# SCH_555-Circuit_2025-10-18.net
KiCad netlist of a schematic drawn in EasyEDA
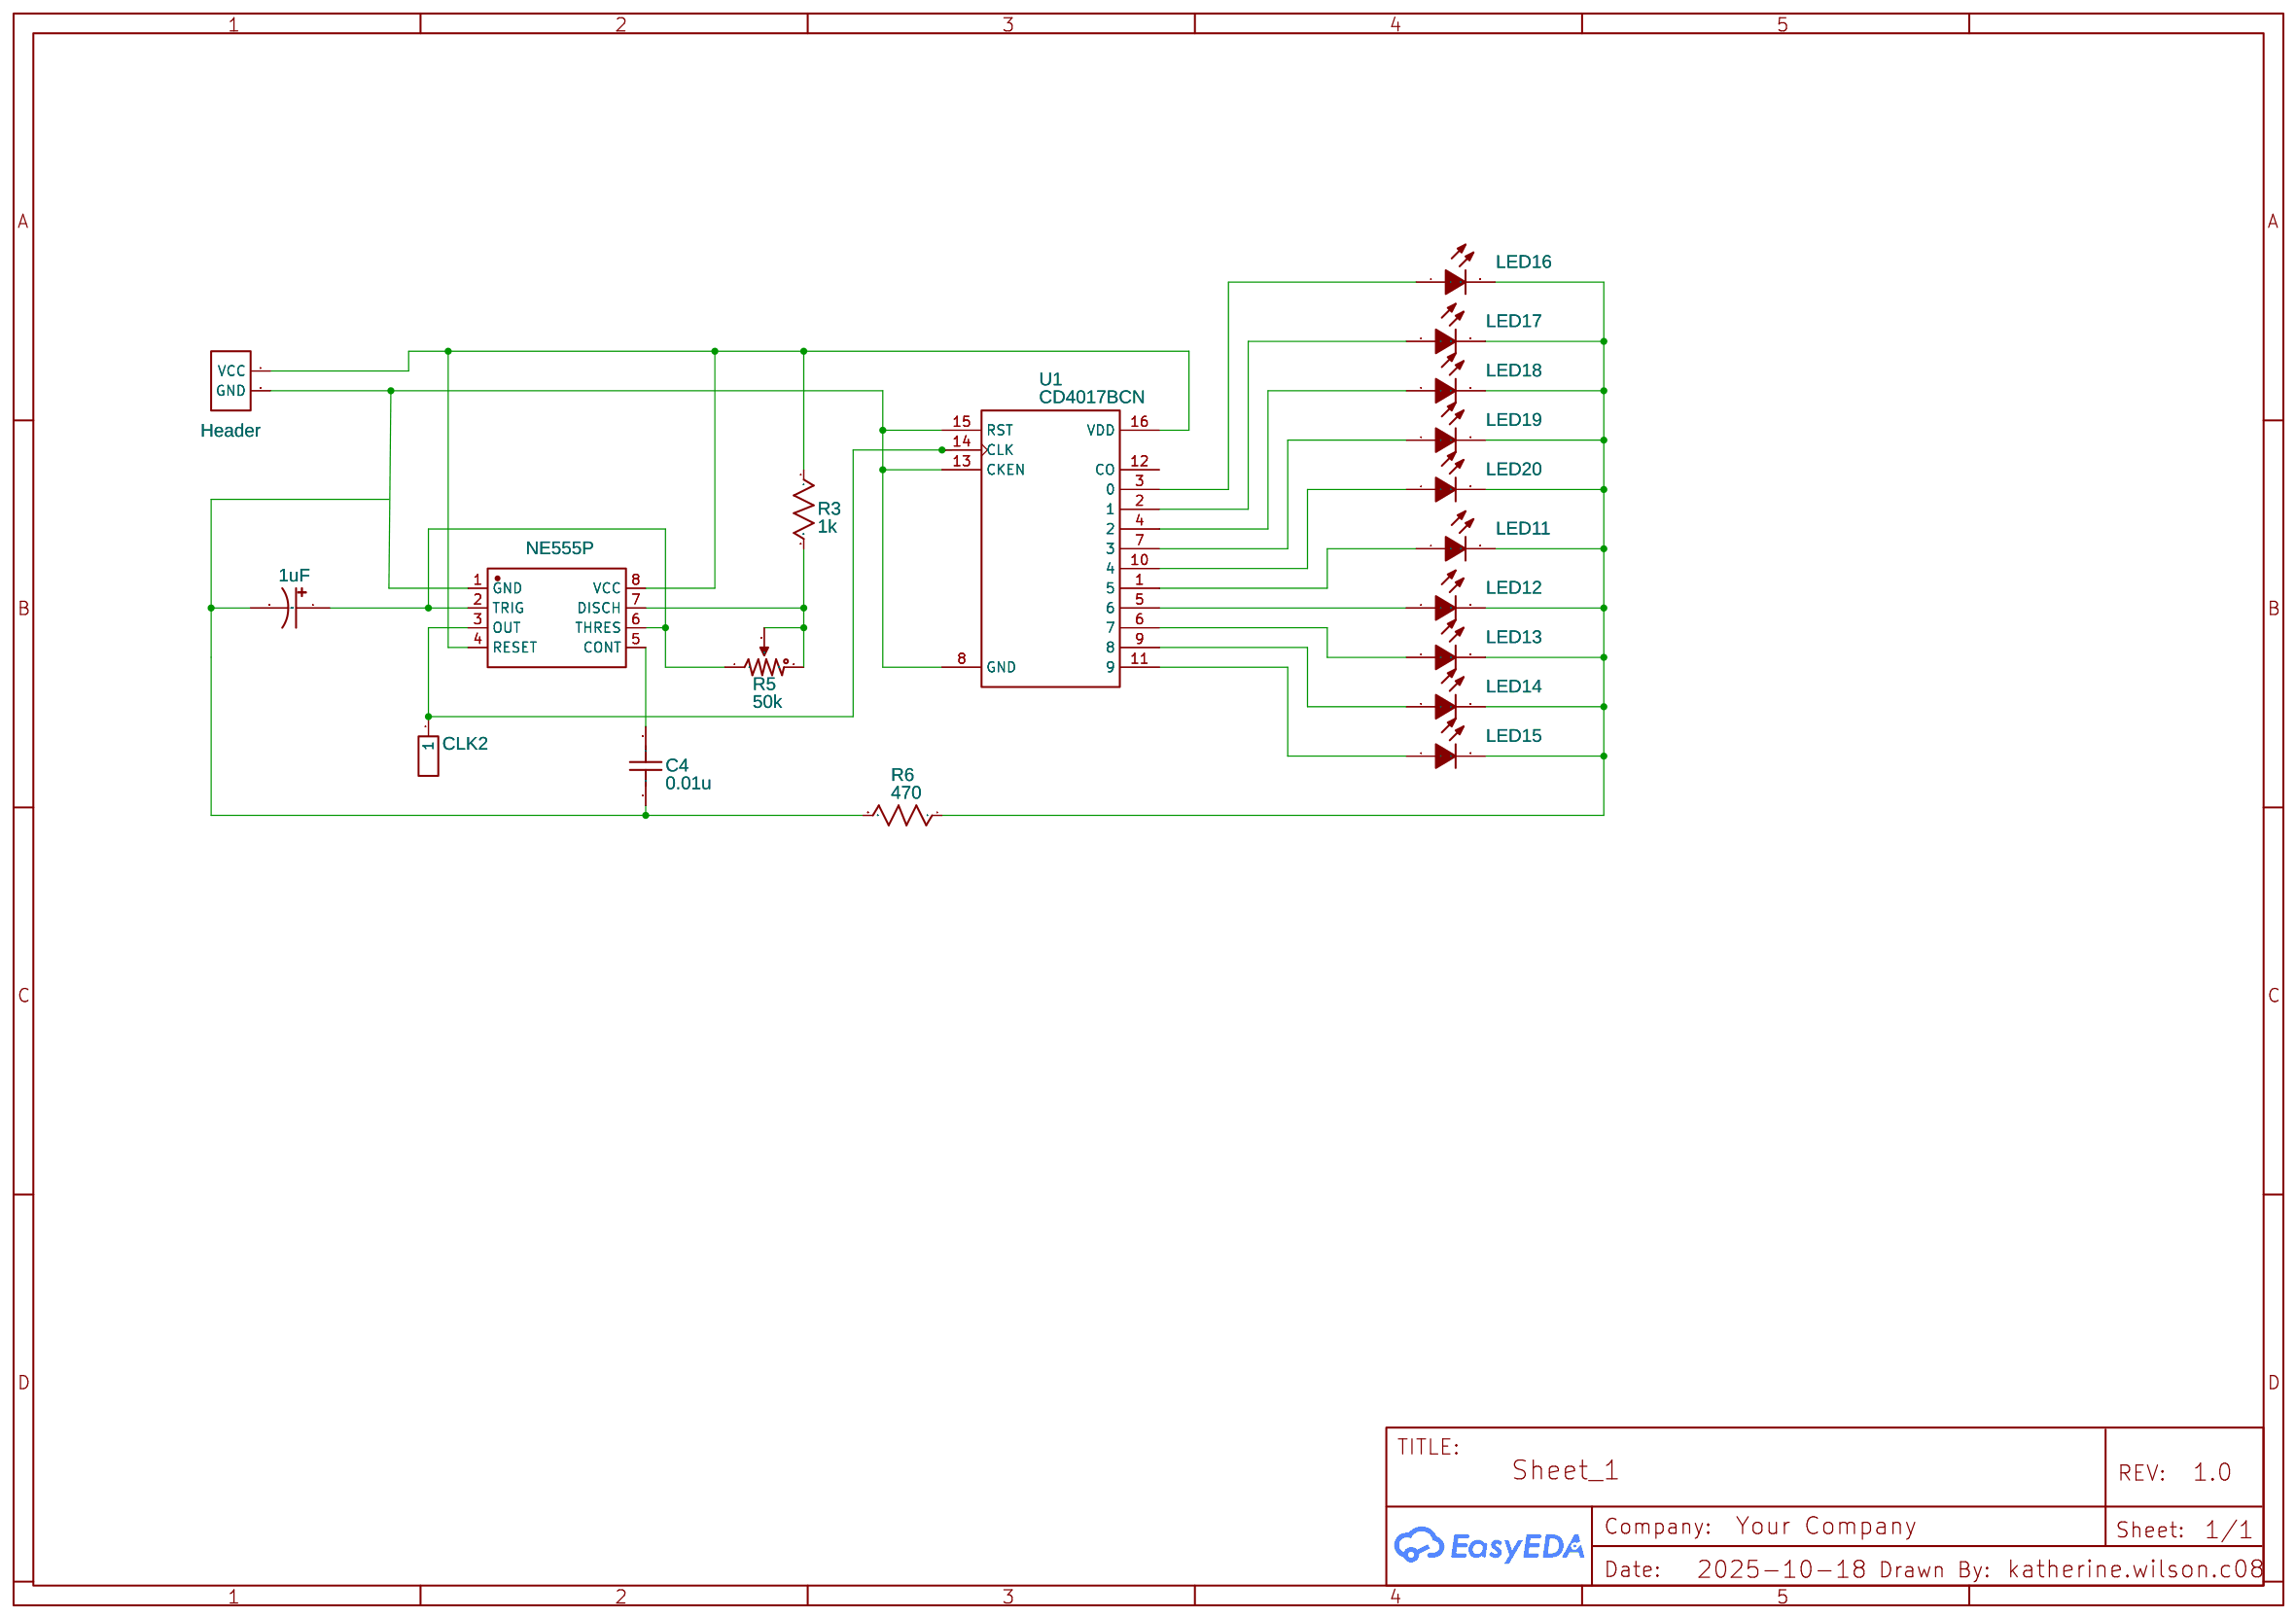
[diagram p0: schematic sheet]

(export (version "E")
  (design (tool "Eeschema 10.0.6"))
  (components
    (comp (ref "C3")
      (value "1uF")
      (fields (field (name "Manufacturer Part") "UVZ1H010MDD") (field (name "Manufacturer") "Nichicon(尼吉康)"))
      (libsource (lib "") (part "UVZ1H010MDD"))
    )
    (comp (ref "C4") (value "0.01u") (libsource (lib "") (part "C_0603_US")))
    (comp (ref "CLK2")
      (value "C81276")
      (fields
        (field (name "Manufacturer Part") "2.54-1*1P针")
        (field (name "Manufacturer") "BOOMELE(Boom Precision Elec)")
      )
      (libsource (lib "") (part "Header-Male-2.54_1x1"))
    )
    (comp (ref "H2") (value "Header") (libsource (lib "") (part "HEADER-FEMALE-2.54_1X2")))
    (comp (ref "LED11") (value "LED_5MM") (libsource (lib "") (part "LED_5MM")))
    (comp (ref "LED12") (value "LED_5MM") (libsource (lib "") (part "LED_5MM")))
    (comp (ref "LED13") (value "LED_5MM") (libsource (lib "") (part "LED_5MM")))
    (comp (ref "LED14") (value "LED_5MM") (libsource (lib "") (part "LED_5MM")))
    (comp (ref "LED15") (value "LED_5MM") (libsource (lib "") (part "LED_5MM")))
    (comp (ref "LED16") (value "LED_5MM") (libsource (lib "") (part "LED_5MM")))
    (comp (ref "LED17") (value "LED_5MM") (libsource (lib "") (part "LED_5MM")))
    (comp (ref "LED18") (value "LED_5MM") (libsource (lib "") (part "LED_5MM")))
    (comp (ref "LED19") (value "LED_5MM") (libsource (lib "") (part "LED_5MM")))
    (comp (ref "LED20") (value "LED_5MM") (libsource (lib "") (part "LED_5MM")))
    (comp (ref "R3")
      (value "1k")
      (fields (field (name "Manufacturer Part") "?"))
      (libsource (lib "") (part "Resistor_1"))
    )
    (comp (ref "R5")
      (value "50k")
      (fields (field (name "Manufacturer Part") "?"))
      (libsource (lib "") (part "Potentiometer"))
    )
    (comp (ref "R6")
      (value "470")
      (fields (field (name "Manufacturer Part") "?"))
      (libsource (lib "") (part "Resistor"))
    )
    (comp (ref "U1") (value "CD4017BCN") (libsource (lib "") (part "CD4017BCN")))
    (comp (ref "U3")
      (value "NE555P")
      (fields (field (name "Manufacturer") "TI(德州仪器)"))
      (libsource (lib "") (part "NE555P"))
    )
  )
  (nets
    (net (code "1") (name "Net-(C3-Pad2)") (class "Default")
      (node (ref "C3") (pin "2") (pinfunction "2_2") (pintype "unspecified"))
      (node (ref "C4") (pin "1") (pinfunction "1_1") (pintype "unspecified"))
      (node (ref "R6") (pin "2") (pinfunction "2_2") (pintype "unspecified"))
    )
    (net (code "2") (name "Net-(H2-GND)") (class "Default")
      (node (ref "H2") (pin "2") (pinfunction "GND_2") (pintype "unspecified"))
      (node (ref "U1") (pin "13") (pinfunction "CKEN_13") (pintype "unspecified"))
      (node (ref "U1") (pin "15") (pinfunction "RST_15") (pintype "unspecified"))
      (node (ref "U1") (pin "8") (pinfunction "GND_8") (pintype "passive"))
      (node (ref "U3") (pin "1") (pinfunction "GND_1") (pintype "unspecified"))
    )
    (net (code "3") (name "Net-(H2-VCC)") (class "Default")
      (node (ref "H2") (pin "1") (pinfunction "VCC_1") (pintype "unspecified"))
      (node (ref "R3") (pin "1") (pinfunction "1_1") (pintype "unspecified"))
      (node (ref "U1") (pin "16") (pinfunction "VDD_16") (pintype "passive"))
      (node (ref "U3") (pin "4") (pinfunction "RESET_4") (pintype "unspecified"))
      (node (ref "U3") (pin "8") (pinfunction "VCC_8") (pintype "unspecified"))
    )
    (net (code "4") (name "Net-(LED11-A)") (class "Default")
      (node (ref "LED11") (pin "1") (pinfunction "A_1") (pintype "input"))
      (node (ref "U1") (pin "1") (pinfunction "5_1") (pintype "output"))
    )
    (net (code "5") (name "Net-(LED11-K)") (class "Default")
      (node (ref "LED11") (pin "2") (pinfunction "K_2") (pintype "input"))
      (node (ref "LED12") (pin "2") (pinfunction "K_2") (pintype "input"))
      (node (ref "LED13") (pin "2") (pinfunction "K_2") (pintype "input"))
      (node (ref "LED14") (pin "2") (pinfunction "K_2") (pintype "input"))
      (node (ref "LED15") (pin "2") (pinfunction "K_2") (pintype "input"))
      (node (ref "LED16") (pin "2") (pinfunction "K_2") (pintype "input"))
      (node (ref "LED17") (pin "2") (pinfunction "K_2") (pintype "input"))
      (node (ref "LED18") (pin "2") (pinfunction "K_2") (pintype "input"))
      (node (ref "LED19") (pin "2") (pinfunction "K_2") (pintype "input"))
      (node (ref "LED20") (pin "2") (pinfunction "K_2") (pintype "input"))
      (node (ref "R6") (pin "1") (pinfunction "1_1") (pintype "unspecified"))
    )
    (net (code "6") (name "Net-(LED12-A)") (class "Default")
      (node (ref "LED12") (pin "1") (pinfunction "A_1") (pintype "input"))
      (node (ref "U1") (pin "5") (pinfunction "6_5") (pintype "output"))
    )
    (net (code "7") (name "Net-(LED13-A)") (class "Default")
      (node (ref "LED13") (pin "1") (pinfunction "A_1") (pintype "input"))
      (node (ref "U1") (pin "6") (pinfunction "7_6") (pintype "output"))
    )
    (net (code "8") (name "Net-(LED14-A)") (class "Default")
      (node (ref "LED14") (pin "1") (pinfunction "A_1") (pintype "input"))
      (node (ref "U1") (pin "9") (pinfunction "8_9") (pintype "output"))
    )
    (net (code "9") (name "Net-(LED15-A)") (class "Default")
      (node (ref "LED15") (pin "1") (pinfunction "A_1") (pintype "input"))
      (node (ref "U1") (pin "11") (pinfunction "9_11") (pintype "output"))
    )
    (net (code "10") (name "Net-(LED16-A)") (class "Default")
      (node (ref "LED16") (pin "1") (pinfunction "A_1") (pintype "input"))
      (node (ref "U1") (pin "3") (pinfunction "0_3") (pintype "output"))
    )
    (net (code "11") (name "Net-(LED17-A)") (class "Default")
      (node (ref "LED17") (pin "1") (pinfunction "A_1") (pintype "input"))
      (node (ref "U1") (pin "2") (pinfunction "1_2") (pintype "output"))
    )
    (net (code "12") (name "Net-(LED18-A)") (class "Default")
      (node (ref "LED18") (pin "1") (pinfunction "A_1") (pintype "input"))
      (node (ref "U1") (pin "4") (pinfunction "2_4") (pintype "output"))
    )
    (net (code "13") (name "Net-(LED19-A)") (class "Default")
      (node (ref "LED19") (pin "1") (pinfunction "A_1") (pintype "input"))
      (node (ref "U1") (pin "7") (pinfunction "3_7") (pintype "output"))
    )
    (net (code "14") (name "Net-(LED20-A)") (class "Default")
      (node (ref "LED20") (pin "1") (pinfunction "A_1") (pintype "input"))
      (node (ref "U1") (pin "10") (pinfunction "4_10") (pintype "output"))
    )
    (net (code "15") (name "Net-(R5-2)") (class "Default")
      (node (ref "R3") (pin "2") (pinfunction "2_2") (pintype "unspecified"))
      (node (ref "R5") (pin "2") (pinfunction "3_2") (pintype "unspecified"))
      (node (ref "R5") (pin "3") (pinfunction "2_3") (pintype "unspecified"))
      (node (ref "U3") (pin "7") (pinfunction "DISCH_7") (pintype "unspecified"))
    )
    (net (code "16") (name "Net-(U1-CLK)") (class "Default")
      (node (ref "CLK2") (pin "1") (pinfunction "1_1") (pintype "unspecified"))
      (node (ref "U1") (pin "14") (pinfunction "CLK_14") (pintype "unspecified"))
      (node (ref "U3") (pin "3") (pinfunction "OUT_3") (pintype "unspecified"))
    )
    (net (code "17") (name "Net-(U3-CONT)") (class "Default")
      (node (ref "C4") (pin "2") (pinfunction "2_2") (pintype "unspecified"))
      (node (ref "U3") (pin "5") (pinfunction "CONT_5") (pintype "unspecified"))
    )
    (net (code "18") (name "Net-(U3-THRES)") (class "Default")
      (node (ref "C3") (pin "1") (pinfunction "1_1") (pintype "unspecified"))
      (node (ref "R5") (pin "1") (pinfunction "1_1") (pintype "unspecified"))
      (node (ref "U3") (pin "2") (pinfunction "TRIG_2") (pintype "unspecified"))
      (node (ref "U3") (pin "6") (pinfunction "THRES_6") (pintype "unspecified"))
    )
    (net (code "19") (name "unconnected-(U1-CO-Pad12)") (class "Default")
      (node (ref "U1") (pin "12") (pinfunction "CO_12") (pintype "output"))
    )
  )
)
